# InstrumentCluster.net
KiCad netlist of a schematic drawn in Altium Designer
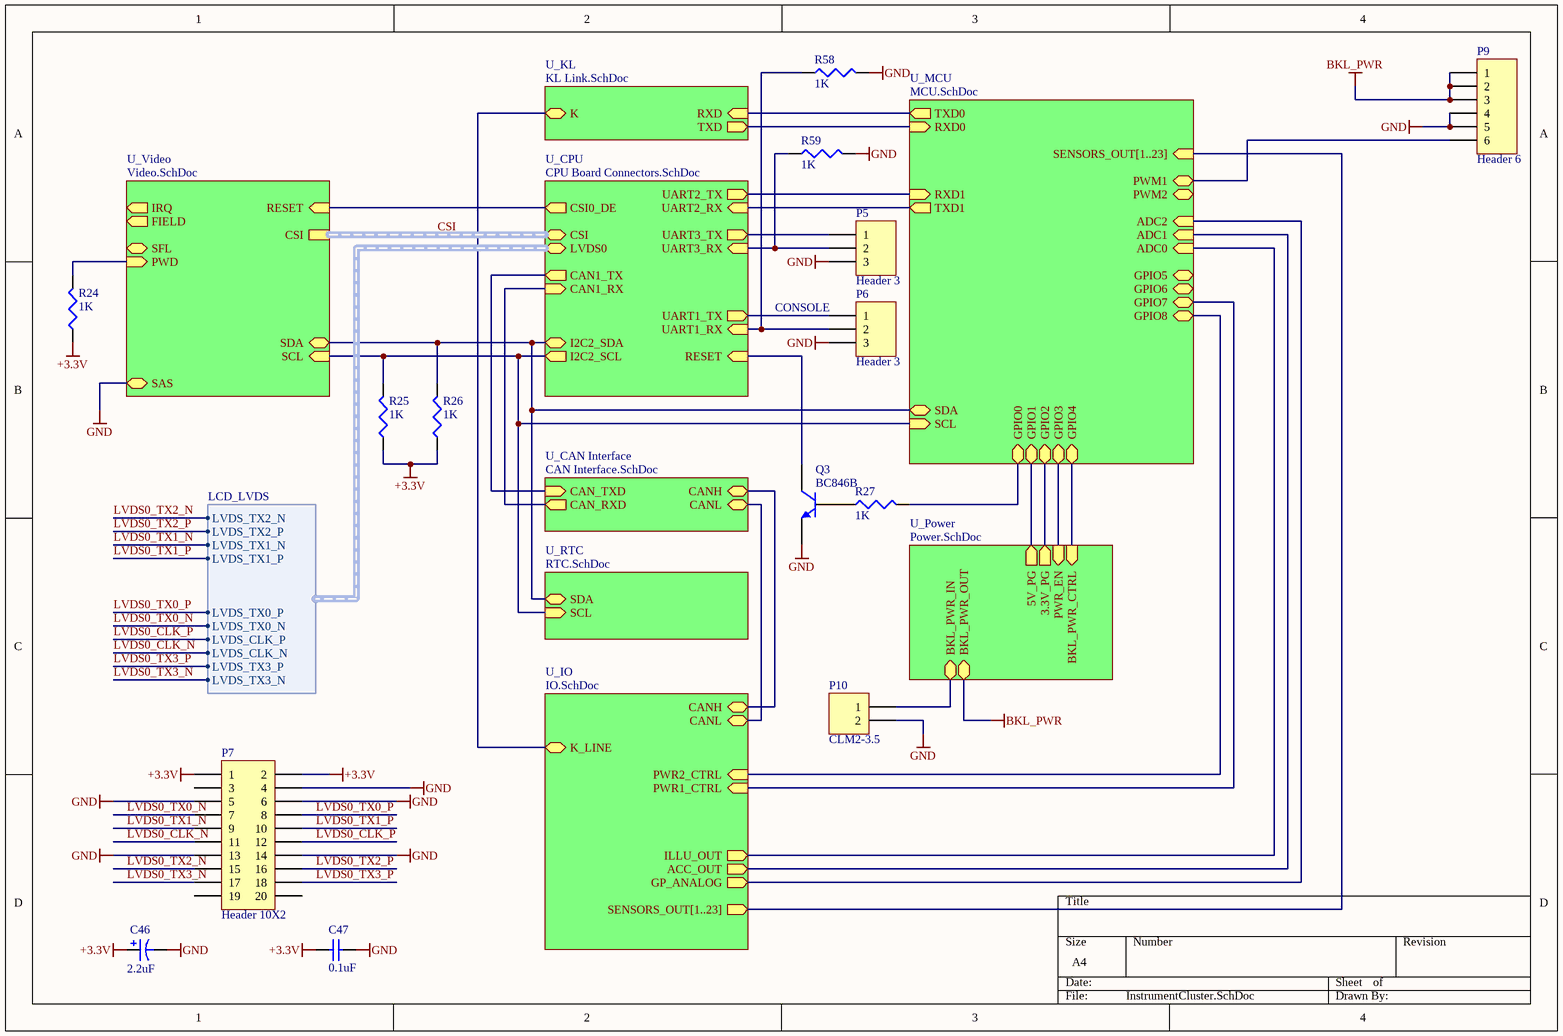
[diagram p0: InstrumentCluster.SchDoc]

(export (version "E")
  (design (tool "Eeschema 10.0.6"))
  (components
    (comp (ref "C46")
      (value "2.2uF")
      (footprint "6032")
      (fields (field (name "PUBLISHER") "Altium Limited"))
      (libsource (lib "Vishay Sprague Tantalum Chip Capacitor") (part "893D225X0025C2"))
    )
    (comp (ref "C47")
      (value "0.1uF")
      (footprint "2012[0805]")
      (description "Ceramic Chip Capacitor - Standard")
      (fields (field (name "PUBLISHER") "Altium Limited"))
      (libsource (lib "ResAndCaps") (part "C0805"))
    )
    (comp (ref "P5")
      (value "Header 3")
      (footprint "HDR1X3")
      (description "Header, 3-Pin")
      (fields (field (name "PUBLISHER") "Altium Limited"))
      (libsource (lib "Miscellaneous Connectors") (part "Header 3"))
    )
    (comp (ref "P6")
      (value "Header 3")
      (footprint "HDR1X3")
      (description "Header, 3-Pin")
      (fields (field (name "PUBLISHER") "Altium Limited"))
      (libsource (lib "Miscellaneous Connectors") (part "Header 3"))
    )
    (comp (ref "P7")
      (value "Header 10X2")
      (footprint "HDR2X10")
      (description "Header, 10-Pin, Dual row")
      (fields (field (name "PUBLISHER") "Altium Limited"))
      (libsource (lib "Miscellaneous Connectors") (part "Header 10X2"))
    )
    (comp (ref "P9")
      (value "Header 6")
      (footprint "HDR1X6")
      (description "Header, 6-Pin")
      (fields (field (name "PUBLISHER") "Altium Limited"))
      (libsource (lib "Miscellaneous Connectors") (part "Header 6"))
    )
    (comp (ref "P10")
      (value "CLM2-3.5")
      (footprint "CLM2-3.5")
      (libsource (lib "connectors") (part "CLM2-3.5"))
    )
    (comp (ref "Q3")
      (value "BC846B")
      (footprint "SOT23_N")
      (description "NPN General-purpose Transistor")
      (fields (field (name "PUBLISHER") "Altium Limited"))
      (libsource (lib "Philips Discrete BJT - Low Power") (part "BC846B"))
    )
    (comp (ref "R24")
      (value "1K")
      (footprint "R2012[0805]")
      (description "R0805")
      (fields (field (name "PUBLISHER") "Altium Limited"))
      (libsource (lib "ResAndCaps") (part "R0805"))
    )
    (comp (ref "R25")
      (value "1K")
      (footprint "R2012[0805]")
      (description "R0805")
      (fields (field (name "PUBLISHER") "Altium Limited"))
      (libsource (lib "ResAndCaps") (part "R0805"))
    )
    (comp (ref "R26")
      (value "1K")
      (footprint "R2012[0805]")
      (description "R0805")
      (fields (field (name "PUBLISHER") "Altium Limited"))
      (libsource (lib "ResAndCaps") (part "R0805"))
    )
    (comp (ref "R27")
      (value "1K")
      (footprint "R2012[0805]")
      (description "R0805")
      (fields (field (name "PUBLISHER") "Altium Limited"))
      (libsource (lib "ResAndCaps") (part "R0805"))
    )
    (comp (ref "R58")
      (value "1K")
      (footprint "R2012[0805]")
      (description "R0805")
      (fields (field (name "PUBLISHER") "Altium Limited"))
      (libsource (lib "ResAndCaps") (part "R0805"))
    )
    (comp (ref "R59")
      (value "1K")
      (footprint "R2012[0805]")
      (description "R0805")
      (fields (field (name "PUBLISHER") "Altium Limited"))
      (libsource (lib "ResAndCaps") (part "R0805"))
    )
  )
  (nets
    (net (code "3") (name "+3.3V") (class "Default")
      (node (ref "C46") (pin "1") (pinfunction "1_1") (pintype "passive"))
      (node (ref "C47") (pin "2") (pinfunction "2_2") (pintype "passive"))
      (node (ref "P7") (pin "1") (pinfunction "1_1") (pintype "passive"))
      (node (ref "P7") (pin "2") (pinfunction "2_2") (pintype "passive"))
      (node (ref "R24") (pin "1") (pinfunction "1_1") (pintype "passive"))
      (node (ref "R25") (pin "1") (pinfunction "1_1") (pintype "passive"))
      (node (ref "R26") (pin "1") (pinfunction "1_1") (pintype "passive"))
    )
    (net (code "8") (name "/BKL_PWR_IN") (class "Default")
      (node (ref "P10") (pin "1") (pinfunction "1_1") (pintype "passive"))
    )
    (net (code "15") (name "/GPIO0") (class "Default")
      (node (ref "R27") (pin "2") (pinfunction "2_2") (pintype "passive"))
    )
    (net (code "22") (name "/I2C2_SCL") (class "Default")
      (node (ref "R25") (pin "2") (pinfunction "2_2") (pintype "passive"))
    )
    (net (code "23") (name "/I2C2_SDA") (class "Default")
      (node (ref "R26") (pin "2") (pinfunction "2_2") (pintype "passive"))
    )
    (net (code "27") (name "/LVDS0_CLK_N") (class "Default")
      (node (ref "P7") (pin "11") (pinfunction "11_11") (pintype "passive"))
    )
    (net (code "28") (name "/LVDS0_CLK_P") (class "Default")
      (node (ref "P7") (pin "12") (pinfunction "12_12") (pintype "passive"))
    )
    (net (code "29") (name "/LVDS0_TX0_N") (class "Default")
      (node (ref "P7") (pin "7") (pinfunction "7_7") (pintype "passive"))
    )
    (net (code "30") (name "/LVDS0_TX0_P") (class "Default")
      (node (ref "P7") (pin "8") (pinfunction "8_8") (pintype "passive"))
    )
    (net (code "31") (name "/LVDS0_TX1_N") (class "Default")
      (node (ref "P7") (pin "9") (pinfunction "9_9") (pintype "passive"))
    )
    (net (code "32") (name "/LVDS0_TX1_P") (class "Default")
      (node (ref "P7") (pin "10") (pinfunction "10_10") (pintype "passive"))
    )
    (net (code "33") (name "/LVDS0_TX2_N") (class "Default")
      (node (ref "P7") (pin "15") (pinfunction "15_15") (pintype "passive"))
    )
    (net (code "34") (name "/LVDS0_TX2_P") (class "Default")
      (node (ref "P7") (pin "16") (pinfunction "16_16") (pintype "passive"))
    )
    (net (code "35") (name "/LVDS0_TX3_N") (class "Default")
      (node (ref "P7") (pin "17") (pinfunction "17_17") (pintype "passive"))
    )
    (net (code "36") (name "/LVDS0_TX3_P") (class "Default")
      (node (ref "P7") (pin "18") (pinfunction "18_18") (pintype "passive"))
    )
    (net (code "37") (name "/PWD") (class "Default")
      (node (ref "R24") (pin "2") (pinfunction "2_2") (pintype "passive"))
    )
    (net (code "38") (name "/PWM1") (class "Default")
      (node (ref "P9") (pin "6") (pinfunction "6_6") (pintype "passive"))
    )
    (net (code "40") (name "/RESET") (class "Default")
      (node (ref "Q3") (pin "3") (pinfunction "C_3") (pintype "passive"))
    )
    (net (code "46") (name "/UART1_RX") (class "Default")
      (node (ref "P6") (pin "2") (pinfunction "2_2") (pintype "passive"))
      (node (ref "R58") (pin "1") (pinfunction "1_1") (pintype "passive"))
    )
    (net (code "47") (name "/UART1_TX") (class "Default")
      (node (ref "P6") (pin "1") (pinfunction "1_1") (pintype "passive"))
    )
    (net (code "49") (name "/UART3_RX") (class "Default")
      (node (ref "P5") (pin "2") (pinfunction "2_2") (pintype "passive"))
      (node (ref "R59") (pin "1") (pinfunction "1_1") (pintype "passive"))
    )
    (net (code "50") (name "/UART3_TX") (class "Default")
      (node (ref "P5") (pin "1") (pinfunction "1_1") (pintype "passive"))
    )
    (net (code "53") (name "BKL_PWR") (class "Default")
      (node (ref "P9") (pin "1") (pinfunction "1_1") (pintype "passive"))
      (node (ref "P9") (pin "2") (pinfunction "2_2") (pintype "passive"))
      (node (ref "P9") (pin "3") (pinfunction "3_3") (pintype "passive"))
    )
    (net (code "54") (name "GND") (class "Default")
      (node (ref "C46") (pin "2") (pinfunction "2_2") (pintype "passive"))
      (node (ref "C47") (pin "1") (pinfunction "1_1") (pintype "passive"))
      (node (ref "P10") (pin "2") (pinfunction "2_2") (pintype "passive"))
      (node (ref "P5") (pin "3") (pinfunction "3_3") (pintype "passive"))
      (node (ref "P6") (pin "3") (pinfunction "3_3") (pintype "passive"))
      (node (ref "P7") (pin "13") (pinfunction "13_13") (pintype "passive"))
      (node (ref "P7") (pin "14") (pinfunction "14_14") (pintype "passive"))
      (node (ref "P7") (pin "4") (pinfunction "4_4") (pintype "passive"))
      (node (ref "P7") (pin "5") (pinfunction "5_5") (pintype "passive"))
      (node (ref "P7") (pin "6") (pinfunction "6_6") (pintype "passive"))
      (node (ref "P9") (pin "4") (pinfunction "4_4") (pintype "passive"))
      (node (ref "P9") (pin "5") (pinfunction "5_5") (pintype "passive"))
      (node (ref "Q3") (pin "2") (pinfunction "E_2") (pintype "passive"))
      (node (ref "R58") (pin "2") (pinfunction "2_2") (pintype "passive"))
      (node (ref "R59") (pin "2") (pinfunction "2_2") (pintype "passive"))
    )
    (net (code "55") (name "Net-(Q3-B)") (class "Default")
      (node (ref "Q3") (pin "1") (pinfunction "B_1") (pintype "passive"))
      (node (ref "R27") (pin "1") (pinfunction "1_1") (pintype "passive"))
    )
    (net (code "56") (name "unconnected-(P7-Pad3)") (class "Default")
      (node (ref "P7") (pin "3") (pinfunction "3_3") (pintype "passive"))
    )
    (net (code "57") (name "unconnected-(P7-Pad19)") (class "Default")
      (node (ref "P7") (pin "19") (pinfunction "19_19") (pintype "passive"))
    )
    (net (code "58") (name "unconnected-(P7-Pad20)") (class "Default")
      (node (ref "P7") (pin "20") (pinfunction "20_20") (pintype "passive"))
    )
  )
)
